# NetworkSwitch.net
KiCad netlist of a schematic drawn in Altium Designer
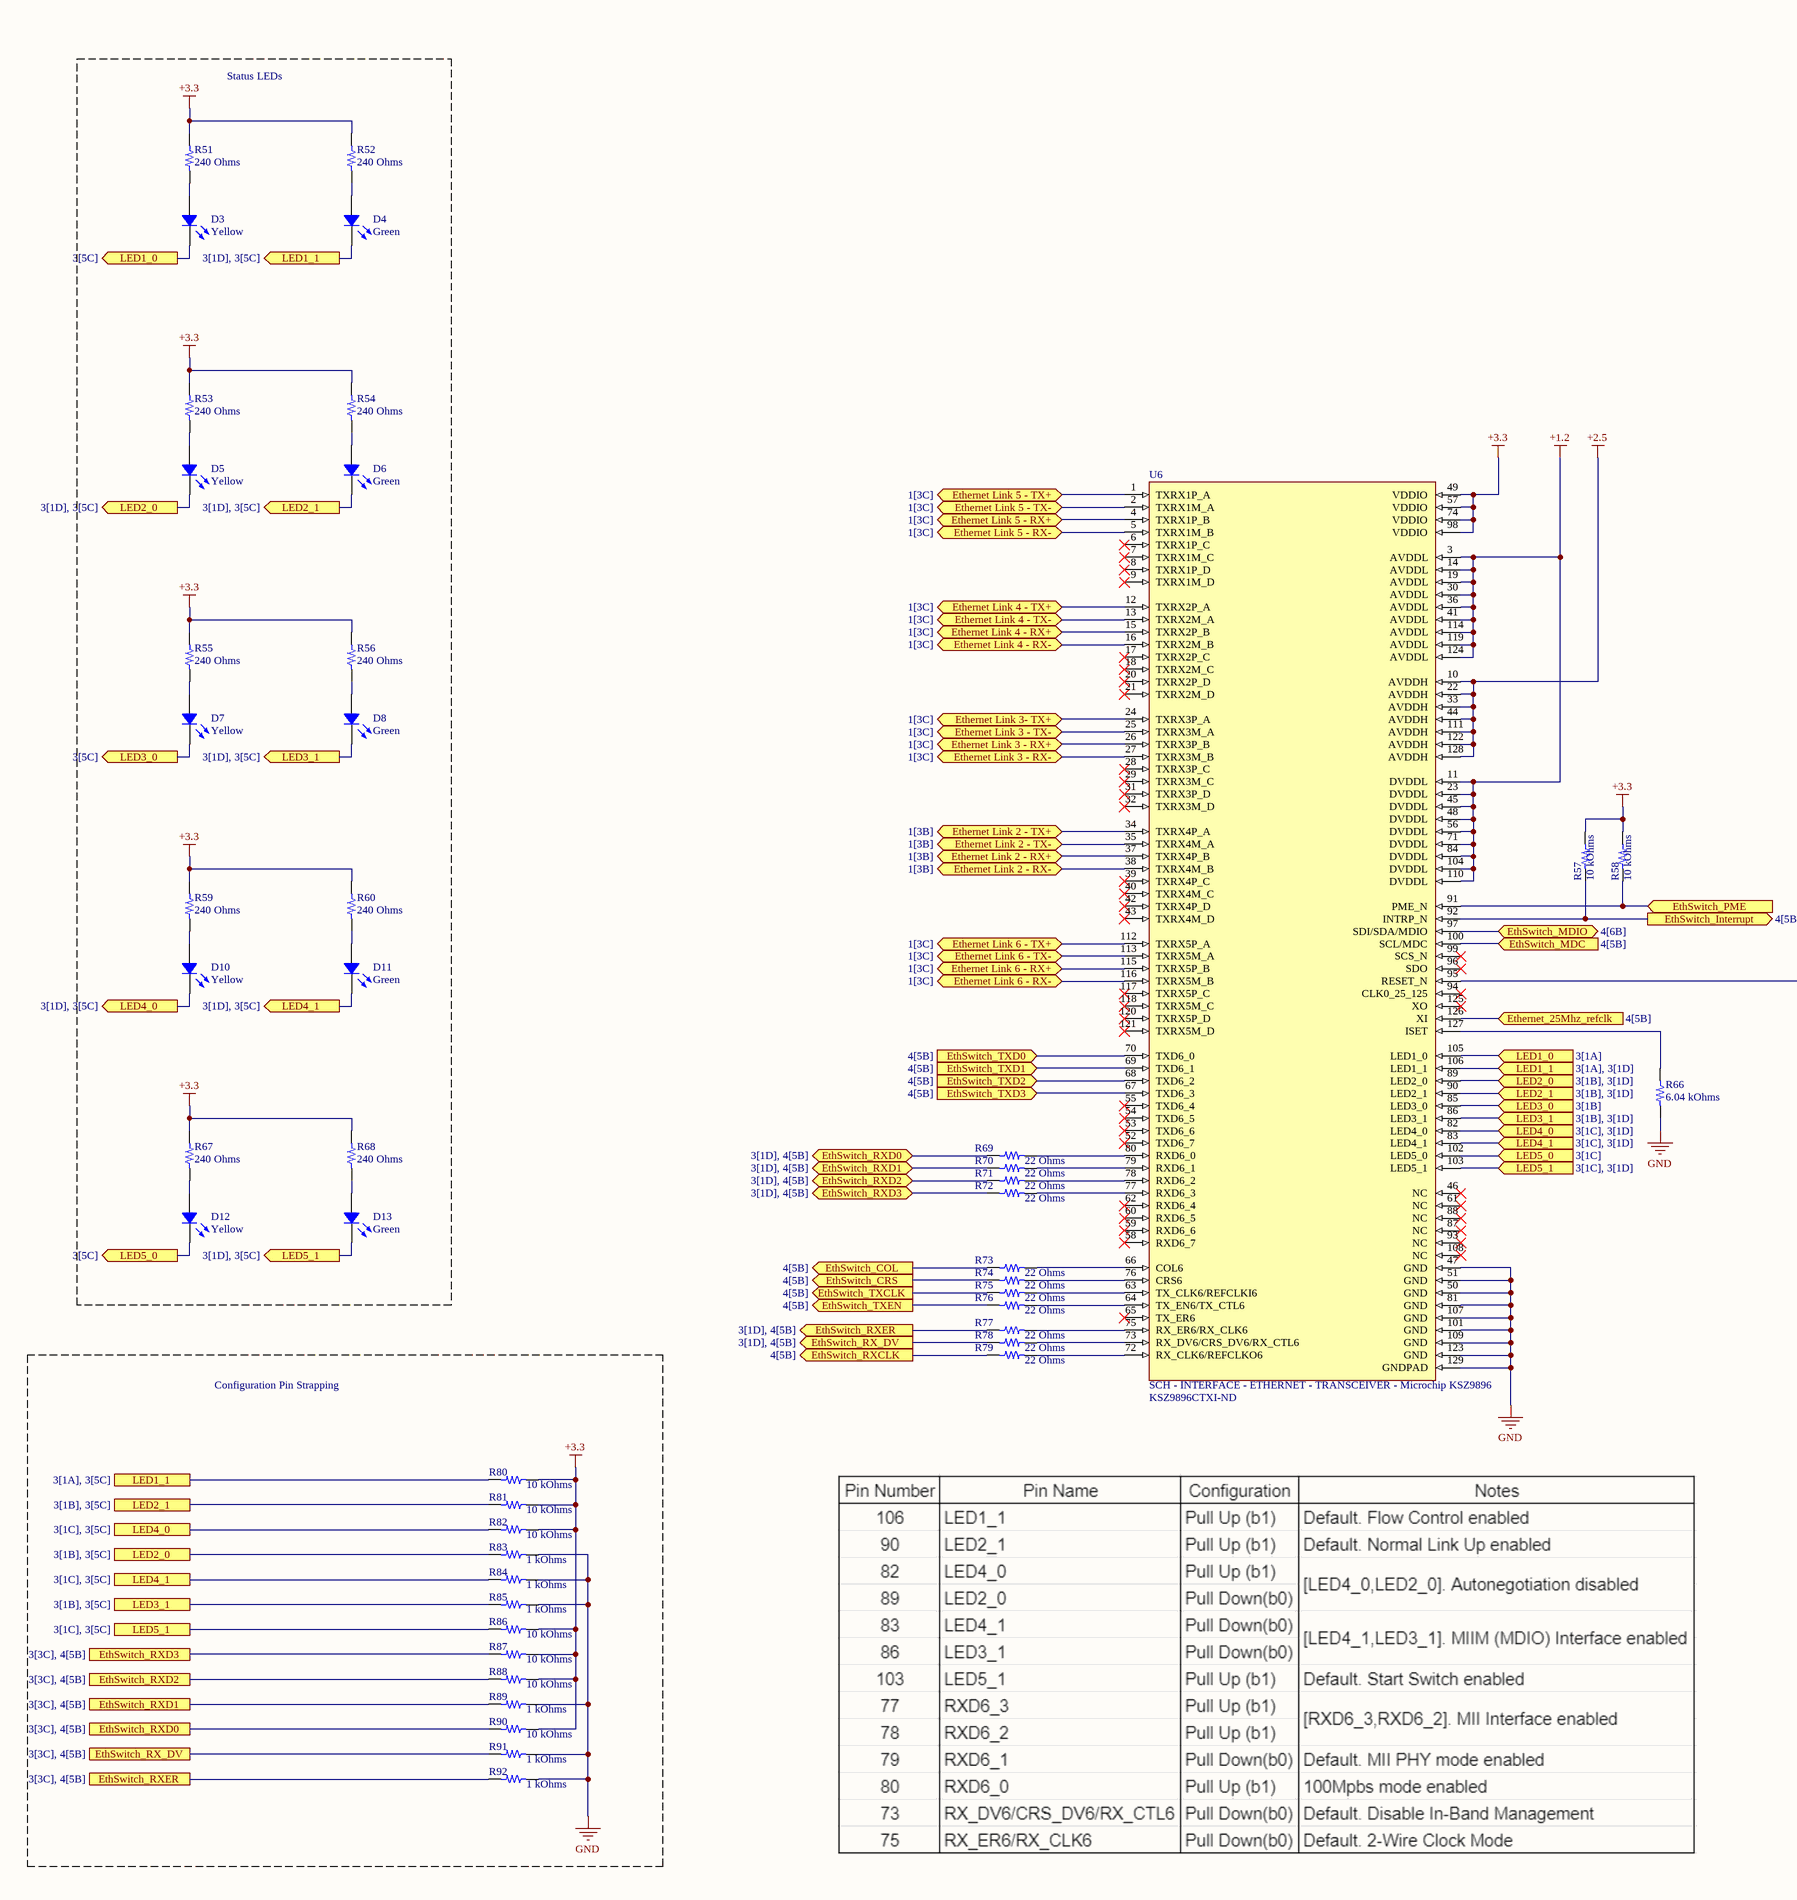
[diagram p0: NetworkSwitch.SchDoc, left]
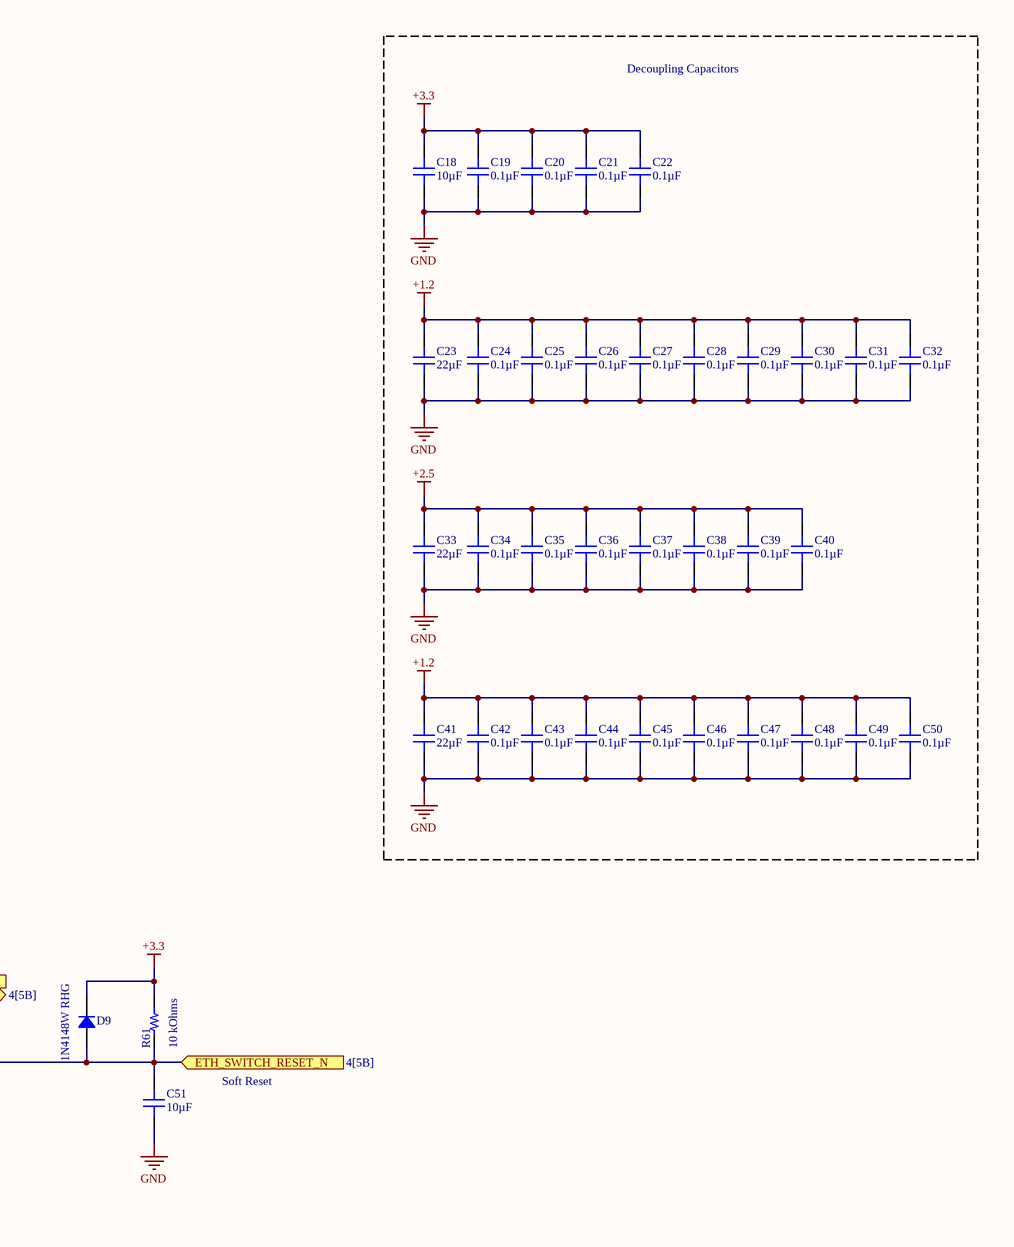
[diagram p1: NetworkSwitch.SchDoc, right]

(export (version "E")
  (design (tool "Eeschema 10.0.6"))
  (components
    (comp (ref "C18")
      (value "10µF")
      (footprint "CAP 0805_2012")
      (description "CAP CER 10UF 16V X5R 0805")
      (fields (field (name "PART NUMBER") "CC0805KKX5R7BB106") (field (name "MANUFACTURER") "Yageo"))
      (libsource (lib "Celestial Altium Library - altium_library") (part "Capacitor"))
    )
    (comp (ref "C19")
      (value "0.1µF")
      (footprint "CAP 0603_1608")
      (description "CAP CER 0.1UF 25V X7R 0603")
      (fields
        (field (name "PART NUMBER") "CL10B104KA8WPNC")
        (field (name "MANUFACTURER") "Samsung Electro-Mechanics")
      )
      (libsource (lib "Celestial Altium Library - altium_library") (part "Capacitor"))
    )
    (comp (ref "C20")
      (value "0.1µF")
      (footprint "CAP 0603_1608")
      (description "CAP CER 0.1UF 25V X7R 0603")
      (fields
        (field (name "PART NUMBER") "CL10B104KA8WPNC")
        (field (name "MANUFACTURER") "Samsung Electro-Mechanics")
      )
      (libsource (lib "Celestial Altium Library - altium_library") (part "Capacitor"))
    )
    (comp (ref "C21")
      (value "0.1µF")
      (footprint "CAP 0603_1608")
      (description "CAP CER 0.1UF 25V X7R 0603")
      (fields
        (field (name "PART NUMBER") "CL10B104KA8WPNC")
        (field (name "MANUFACTURER") "Samsung Electro-Mechanics")
      )
      (libsource (lib "Celestial Altium Library - altium_library") (part "Capacitor"))
    )
    (comp (ref "C22")
      (value "0.1µF")
      (footprint "CAP 0603_1608")
      (description "CAP CER 0.1UF 25V X7R 0603")
      (fields
        (field (name "PART NUMBER") "CL10B104KA8WPNC")
        (field (name "MANUFACTURER") "Samsung Electro-Mechanics")
      )
      (libsource (lib "Celestial Altium Library - altium_library") (part "Capacitor"))
    )
    (comp (ref "C23")
      (value "22µF")
      (footprint "CAP 0805_2012")
      (description "CAP CER 22UF 10V X5R 0805")
      (fields
        (field (name "PART NUMBER") "CL21A226KPCLRNC")
        (field (name "MANUFACTURER") "Samsung Electro-Mechanics")
      )
      (libsource (lib "Celestial Altium Library - altium_library") (part "Capacitor"))
    )
    (comp (ref "C24")
      (value "0.1µF")
      (footprint "CAP 0603_1608")
      (description "CAP CER 0.1UF 25V X7R 0603")
      (fields
        (field (name "PART NUMBER") "CL10B104KA8WPNC")
        (field (name "MANUFACTURER") "Samsung Electro-Mechanics")
      )
      (libsource (lib "Celestial Altium Library - altium_library") (part "Capacitor"))
    )
    (comp (ref "C25")
      (value "0.1µF")
      (footprint "CAP 0603_1608")
      (description "CAP CER 0.1UF 25V X7R 0603")
      (fields
        (field (name "PART NUMBER") "CL10B104KA8WPNC")
        (field (name "MANUFACTURER") "Samsung Electro-Mechanics")
      )
      (libsource (lib "Celestial Altium Library - altium_library") (part "Capacitor"))
    )
    (comp (ref "C26")
      (value "0.1µF")
      (footprint "CAP 0603_1608")
      (description "CAP CER 0.1UF 25V X7R 0603")
      (fields
        (field (name "PART NUMBER") "CL10B104KA8WPNC")
        (field (name "MANUFACTURER") "Samsung Electro-Mechanics")
      )
      (libsource (lib "Celestial Altium Library - altium_library") (part "Capacitor"))
    )
    (comp (ref "C27")
      (value "0.1µF")
      (footprint "CAP 0603_1608")
      (description "CAP CER 0.1UF 25V X7R 0603")
      (fields
        (field (name "PART NUMBER") "CL10B104KA8WPNC")
        (field (name "MANUFACTURER") "Samsung Electro-Mechanics")
      )
      (libsource (lib "Celestial Altium Library - altium_library") (part "Capacitor"))
    )
    (comp (ref "C28")
      (value "0.1µF")
      (footprint "CAP 0603_1608")
      (description "CAP CER 0.1UF 25V X7R 0603")
      (fields
        (field (name "PART NUMBER") "CL10B104KA8WPNC")
        (field (name "MANUFACTURER") "Samsung Electro-Mechanics")
      )
      (libsource (lib "Celestial Altium Library - altium_library") (part "Capacitor"))
    )
    (comp (ref "C29")
      (value "0.1µF")
      (footprint "CAP 0603_1608")
      (description "CAP CER 0.1UF 25V X7R 0603")
      (fields
        (field (name "PART NUMBER") "CL10B104KA8WPNC")
        (field (name "MANUFACTURER") "Samsung Electro-Mechanics")
      )
      (libsource (lib "Celestial Altium Library - altium_library") (part "Capacitor"))
    )
    (comp (ref "C30")
      (value "0.1µF")
      (footprint "CAP 0603_1608")
      (description "CAP CER 0.1UF 25V X7R 0603")
      (fields
        (field (name "PART NUMBER") "CL10B104KA8WPNC")
        (field (name "MANUFACTURER") "Samsung Electro-Mechanics")
      )
      (libsource (lib "Celestial Altium Library - altium_library") (part "Capacitor"))
    )
    (comp (ref "C31")
      (value "0.1µF")
      (footprint "CAP 0603_1608")
      (description "CAP CER 0.1UF 25V X7R 0603")
      (fields
        (field (name "PART NUMBER") "CL10B104KA8WPNC")
        (field (name "MANUFACTURER") "Samsung Electro-Mechanics")
      )
      (libsource (lib "Celestial Altium Library - altium_library") (part "Capacitor"))
    )
    (comp (ref "C32")
      (value "0.1µF")
      (footprint "CAP 0603_1608")
      (description "CAP CER 0.1UF 25V X7R 0603")
      (fields
        (field (name "PART NUMBER") "CL10B104KA8WPNC")
        (field (name "MANUFACTURER") "Samsung Electro-Mechanics")
      )
      (libsource (lib "Celestial Altium Library - altium_library") (part "Capacitor"))
    )
    (comp (ref "C33")
      (value "22µF")
      (footprint "CAP 0805_2012")
      (description "CAP CER 22UF 10V X5R 0805")
      (fields
        (field (name "PART NUMBER") "CL21A226KPCLRNC")
        (field (name "MANUFACTURER") "Samsung Electro-Mechanics")
      )
      (libsource (lib "Celestial Altium Library - altium_library") (part "Capacitor"))
    )
    (comp (ref "C34")
      (value "0.1µF")
      (footprint "CAP 0603_1608")
      (description "CAP CER 0.1UF 25V X7R 0603")
      (fields
        (field (name "PART NUMBER") "CL10B104KA8WPNC")
        (field (name "MANUFACTURER") "Samsung Electro-Mechanics")
      )
      (libsource (lib "Celestial Altium Library - altium_library") (part "Capacitor"))
    )
    (comp (ref "C35")
      (value "0.1µF")
      (footprint "CAP 0603_1608")
      (description "CAP CER 0.1UF 25V X7R 0603")
      (fields
        (field (name "PART NUMBER") "CL10B104KA8WPNC")
        (field (name "MANUFACTURER") "Samsung Electro-Mechanics")
      )
      (libsource (lib "Celestial Altium Library - altium_library") (part "Capacitor"))
    )
    (comp (ref "C36")
      (value "0.1µF")
      (footprint "CAP 0603_1608")
      (description "CAP CER 0.1UF 25V X7R 0603")
      (fields
        (field (name "PART NUMBER") "CL10B104KA8WPNC")
        (field (name "MANUFACTURER") "Samsung Electro-Mechanics")
      )
      (libsource (lib "Celestial Altium Library - altium_library") (part "Capacitor"))
    )
    (comp (ref "C37")
      (value "0.1µF")
      (footprint "CAP 0603_1608")
      (description "CAP CER 0.1UF 25V X7R 0603")
      (fields
        (field (name "PART NUMBER") "CL10B104KA8WPNC")
        (field (name "MANUFACTURER") "Samsung Electro-Mechanics")
      )
      (libsource (lib "Celestial Altium Library - altium_library") (part "Capacitor"))
    )
    (comp (ref "C38")
      (value "0.1µF")
      (footprint "CAP 0603_1608")
      (description "CAP CER 0.1UF 25V X7R 0603")
      (fields
        (field (name "PART NUMBER") "CL10B104KA8WPNC")
        (field (name "MANUFACTURER") "Samsung Electro-Mechanics")
      )
      (libsource (lib "Celestial Altium Library - altium_library") (part "Capacitor"))
    )
    (comp (ref "C39")
      (value "0.1µF")
      (footprint "CAP 0603_1608")
      (description "CAP CER 0.1UF 25V X7R 0603")
      (fields
        (field (name "PART NUMBER") "CL10B104KA8WPNC")
        (field (name "MANUFACTURER") "Samsung Electro-Mechanics")
      )
      (libsource (lib "Celestial Altium Library - altium_library") (part "Capacitor"))
    )
    (comp (ref "C40")
      (value "0.1µF")
      (footprint "CAP 0603_1608")
      (description "CAP CER 0.1UF 25V X7R 0603")
      (fields
        (field (name "PART NUMBER") "CL10B104KA8WPNC")
        (field (name "MANUFACTURER") "Samsung Electro-Mechanics")
      )
      (libsource (lib "Celestial Altium Library - altium_library") (part "Capacitor"))
    )
    (comp (ref "C41")
      (value "22µF")
      (footprint "CAP 0805_2012")
      (description "CAP CER 22UF 10V X5R 0805")
      (fields
        (field (name "PART NUMBER") "CL21A226KPCLRNC")
        (field (name "MANUFACTURER") "Samsung Electro-Mechanics")
      )
      (libsource (lib "Celestial Altium Library - altium_library") (part "Capacitor"))
    )
    (comp (ref "C42")
      (value "0.1µF")
      (footprint "CAP 0603_1608")
      (description "CAP CER 0.1UF 25V X7R 0603")
      (fields
        (field (name "PART NUMBER") "CL10B104KA8WPNC")
        (field (name "MANUFACTURER") "Samsung Electro-Mechanics")
      )
      (libsource (lib "Celestial Altium Library - altium_library") (part "Capacitor"))
    )
    (comp (ref "C43")
      (value "0.1µF")
      (footprint "CAP 0603_1608")
      (description "CAP CER 0.1UF 25V X7R 0603")
      (fields
        (field (name "PART NUMBER") "CL10B104KA8WPNC")
        (field (name "MANUFACTURER") "Samsung Electro-Mechanics")
      )
      (libsource (lib "Celestial Altium Library - altium_library") (part "Capacitor"))
    )
    (comp (ref "C44")
      (value "0.1µF")
      (footprint "CAP 0603_1608")
      (description "CAP CER 0.1UF 25V X7R 0603")
      (fields
        (field (name "PART NUMBER") "CL10B104KA8WPNC")
        (field (name "MANUFACTURER") "Samsung Electro-Mechanics")
      )
      (libsource (lib "Celestial Altium Library - altium_library") (part "Capacitor"))
    )
    (comp (ref "C45")
      (value "0.1µF")
      (footprint "CAP 0603_1608")
      (description "CAP CER 0.1UF 25V X7R 0603")
      (fields
        (field (name "PART NUMBER") "CL10B104KA8WPNC")
        (field (name "MANUFACTURER") "Samsung Electro-Mechanics")
      )
      (libsource (lib "Celestial Altium Library - altium_library") (part "Capacitor"))
    )
    (comp (ref "C46")
      (value "0.1µF")
      (footprint "CAP 0603_1608")
      (description "CAP CER 0.1UF 25V X7R 0603")
      (fields
        (field (name "PART NUMBER") "CL10B104KA8WPNC")
        (field (name "MANUFACTURER") "Samsung Electro-Mechanics")
      )
      (libsource (lib "Celestial Altium Library - altium_library") (part "Capacitor"))
    )
    (comp (ref "C47")
      (value "0.1µF")
      (footprint "CAP 0603_1608")
      (description "CAP CER 0.1UF 25V X7R 0603")
      (fields
        (field (name "PART NUMBER") "CL10B104KA8WPNC")
        (field (name "MANUFACTURER") "Samsung Electro-Mechanics")
      )
      (libsource (lib "Celestial Altium Library - altium_library") (part "Capacitor"))
    )
    (comp (ref "C48")
      (value "0.1µF")
      (footprint "CAP 0603_1608")
      (description "CAP CER 0.1UF 25V X7R 0603")
      (fields
        (field (name "PART NUMBER") "CL10B104KA8WPNC")
        (field (name "MANUFACTURER") "Samsung Electro-Mechanics")
      )
      (libsource (lib "Celestial Altium Library - altium_library") (part "Capacitor"))
    )
    (comp (ref "C49")
      (value "0.1µF")
      (footprint "CAP 0603_1608")
      (description "CAP CER 0.1UF 25V X7R 0603")
      (fields
        (field (name "PART NUMBER") "CL10B104KA8WPNC")
        (field (name "MANUFACTURER") "Samsung Electro-Mechanics")
      )
      (libsource (lib "Celestial Altium Library - altium_library") (part "Capacitor"))
    )
    (comp (ref "C50")
      (value "0.1µF")
      (footprint "CAP 0603_1608")
      (description "CAP CER 0.1UF 25V X7R 0603")
      (fields
        (field (name "PART NUMBER") "CL10B104KA8WPNC")
        (field (name "MANUFACTURER") "Samsung Electro-Mechanics")
      )
      (libsource (lib "Celestial Altium Library - altium_library") (part "Capacitor"))
    )
    (comp (ref "C51")
      (value "10µF")
      (footprint "CAP 0805_2012")
      (description "CAP CER 10UF 16V X5R 0805")
      (fields (field (name "PART NUMBER") "CC0805KKX5R7BB106") (field (name "MANUFACTURER") "Yageo"))
      (libsource (lib "Celestial Altium Library - altium_library") (part "Capacitor"))
    )
    (comp (ref "D3")
      (value "Yellow")
      (footprint "LED 0603_1608 YELLOW")
      (description "LED YELLOW CLEAR SMD")
      (fields (field (name "PART NUMBER") "LTST-C191KSKT") (field (name "MANUFACTURER") "Lite-On Inc."))
      (libsource (lib "Celestial Altium Library - altium_library") (part "LED"))
    )
    (comp (ref "D4")
      (value "Green")
      (footprint "LED 0603_1608 GREEN")
      (description "LED GREEN CLEAR CHIP SMD")
      (fields (field (name "PART NUMBER") "LTST-C193KGKT-5A") (field (name "MANUFACTURER") "Lite-On Inc."))
      (libsource (lib "Celestial Altium Library - altium_library") (part "LED"))
    )
    (comp (ref "D5")
      (value "Yellow")
      (footprint "LED 0603_1608 YELLOW")
      (description "LED YELLOW CLEAR SMD")
      (fields (field (name "PART NUMBER") "LTST-C191KSKT") (field (name "MANUFACTURER") "Lite-On Inc."))
      (libsource (lib "Celestial Altium Library - altium_library") (part "LED"))
    )
    (comp (ref "D6")
      (value "Green")
      (footprint "LED 0603_1608 GREEN")
      (description "LED GREEN CLEAR CHIP SMD")
      (fields (field (name "PART NUMBER") "LTST-C193KGKT-5A") (field (name "MANUFACTURER") "Lite-On Inc."))
      (libsource (lib "Celestial Altium Library - altium_library") (part "LED"))
    )
    (comp (ref "D7")
      (value "Yellow")
      (footprint "LED 0603_1608 YELLOW")
      (description "LED YELLOW CLEAR SMD")
      (fields (field (name "PART NUMBER") "LTST-C191KSKT") (field (name "MANUFACTURER") "Lite-On Inc."))
      (libsource (lib "Celestial Altium Library - altium_library") (part "LED"))
    )
    (comp (ref "D8")
      (value "Green")
      (footprint "LED 0603_1608 GREEN")
      (description "LED GREEN CLEAR CHIP SMD")
      (fields (field (name "PART NUMBER") "LTST-C193KGKT-5A") (field (name "MANUFACTURER") "Lite-On Inc."))
      (libsource (lib "Celestial Altium Library - altium_library") (part "LED"))
    )
    (comp (ref "D9")
      (value "1N4148W RHG")
      (footprint "SOD123F")
      (description "DIODE GEN PURP 100V 150MA SOD123")
      (fields (field (name "MANUFACTURER") "Taiwan Semiconductor Corporation"))
      (libsource (lib "Celestial Altium Library - altium_library") (part "Diode"))
    )
    (comp (ref "D10")
      (value "Yellow")
      (footprint "LED 0603_1608 YELLOW")
      (description "LED YELLOW CLEAR SMD")
      (fields (field (name "PART NUMBER") "LTST-C191KSKT") (field (name "MANUFACTURER") "Lite-On Inc."))
      (libsource (lib "Celestial Altium Library - altium_library") (part "LED"))
    )
    (comp (ref "D11")
      (value "Green")
      (footprint "LED 0603_1608 GREEN")
      (description "LED GREEN CLEAR CHIP SMD")
      (fields (field (name "PART NUMBER") "LTST-C193KGKT-5A") (field (name "MANUFACTURER") "Lite-On Inc."))
      (libsource (lib "Celestial Altium Library - altium_library") (part "LED"))
    )
    (comp (ref "D12")
      (value "Yellow")
      (footprint "LED 0603_1608 YELLOW")
      (description "LED YELLOW CLEAR SMD")
      (fields (field (name "PART NUMBER") "LTST-C191KSKT") (field (name "MANUFACTURER") "Lite-On Inc."))
      (libsource (lib "Celestial Altium Library - altium_library") (part "LED"))
    )
    (comp (ref "D13")
      (value "Green")
      (footprint "LED 0603_1608 GREEN")
      (description "LED GREEN CLEAR CHIP SMD")
      (fields (field (name "PART NUMBER") "LTST-C193KGKT-5A") (field (name "MANUFACTURER") "Lite-On Inc."))
      (libsource (lib "Celestial Altium Library - altium_library") (part "LED"))
    )
    (comp (ref "R51")
      (value "240 Ohms")
      (footprint "RES 0603_1608")
      (description "RES 240 OHM 5% 1/10W 0603")
      (fields
        (field (name "PART NUMBER") "RMCF0603JT240R")
        (field (name "MANUFACTURER") "Stackpole Electronics Inc")
      )
      (libsource (lib "Celestial Altium Library - altium_library") (part "Resistor"))
    )
    (comp (ref "R52")
      (value "240 Ohms")
      (footprint "RES 0603_1608")
      (description "RES 240 OHM 5% 1/10W 0603")
      (fields
        (field (name "PART NUMBER") "RMCF0603JT240R")
        (field (name "MANUFACTURER") "Stackpole Electronics Inc")
      )
      (libsource (lib "Celestial Altium Library - altium_library") (part "Resistor"))
    )
    (comp (ref "R53")
      (value "240 Ohms")
      (footprint "RES 0603_1608")
      (description "RES 240 OHM 5% 1/10W 0603")
      (fields
        (field (name "PART NUMBER") "RMCF0603JT240R")
        (field (name "MANUFACTURER") "Stackpole Electronics Inc")
      )
      (libsource (lib "Celestial Altium Library - altium_library") (part "Resistor"))
    )
    (comp (ref "R54")
      (value "240 Ohms")
      (footprint "RES 0603_1608")
      (description "RES 240 OHM 5% 1/10W 0603")
      (fields
        (field (name "PART NUMBER") "RMCF0603JT240R")
        (field (name "MANUFACTURER") "Stackpole Electronics Inc")
      )
      (libsource (lib "Celestial Altium Library - altium_library") (part "Resistor"))
    )
    (comp (ref "R55")
      (value "240 Ohms")
      (footprint "RES 0603_1608")
      (description "RES 240 OHM 5% 1/10W 0603")
      (fields
        (field (name "PART NUMBER") "RMCF0603JT240R")
        (field (name "MANUFACTURER") "Stackpole Electronics Inc")
      )
      (libsource (lib "Celestial Altium Library - altium_library") (part "Resistor"))
    )
    (comp (ref "R56")
      (value "240 Ohms")
      (footprint "RES 0603_1608")
      (description "RES 240 OHM 5% 1/10W 0603")
      (fields
        (field (name "PART NUMBER") "RMCF0603JT240R")
        (field (name "MANUFACTURER") "Stackpole Electronics Inc")
      )
      (libsource (lib "Celestial Altium Library - altium_library") (part "Resistor"))
    )
    (comp (ref "R57")
      (value "10 kOhms")
      (footprint "RES 0603_1608")
      (description "RES 10K OHM 5% 1/10W 0603")
      (fields
        (field (name "PART NUMBER") "RMCF0603JT10K0")
        (field (name "MANUFACTURER") "Stackpole Electronics Inc")
      )
      (libsource (lib "Celestial Altium Library - altium_library") (part "Resistor"))
    )
    (comp (ref "R58")
      (value "10 kOhms")
      (footprint "RES 0603_1608")
      (description "RES 10K OHM 5% 1/10W 0603")
      (fields
        (field (name "PART NUMBER") "RMCF0603JT10K0")
        (field (name "MANUFACTURER") "Stackpole Electronics Inc")
      )
      (libsource (lib "Celestial Altium Library - altium_library") (part "Resistor"))
    )
    (comp (ref "R59")
      (value "240 Ohms")
      (footprint "RES 0603_1608")
      (description "RES 240 OHM 5% 1/10W 0603")
      (fields
        (field (name "PART NUMBER") "RMCF0603JT240R")
        (field (name "MANUFACTURER") "Stackpole Electronics Inc")
      )
      (libsource (lib "Celestial Altium Library - altium_library") (part "Resistor"))
    )
    (comp (ref "R60")
      (value "240 Ohms")
      (footprint "RES 0603_1608")
      (description "RES 240 OHM 5% 1/10W 0603")
      (fields
        (field (name "PART NUMBER") "RMCF0603JT240R")
        (field (name "MANUFACTURER") "Stackpole Electronics Inc")
      )
      (libsource (lib "Celestial Altium Library - altium_library") (part "Resistor"))
    )
    (comp (ref "R61")
      (value "10 kOhms")
      (footprint "RES 0603_1608")
      (description "RES 10K OHM 5% 1/10W 0603")
      (fields
        (field (name "PART NUMBER") "RMCF0603JT10K0")
        (field (name "MANUFACTURER") "Stackpole Electronics Inc")
      )
      (libsource (lib "Celestial Altium Library - altium_library") (part "Resistor"))
    )
    (comp (ref "R66")
      (value "6.04 kOhms")
      (footprint "RES 0603_1608")
      (description "RES 6.04K OHM 1% 1/10W 0603")
      (fields
        (field (name "PART NUMBER") "RMCF0603FT6K04")
        (field (name "MANUFACTURER") "Stackpole Electronics Inc")
      )
      (libsource (lib "Celestial Altium Library - altium_library") (part "Resistor"))
    )
    (comp (ref "R67")
      (value "240 Ohms")
      (footprint "RES 0603_1608")
      (description "RES 240 OHM 5% 1/10W 0603")
      (fields
        (field (name "PART NUMBER") "RMCF0603JT240R")
        (field (name "MANUFACTURER") "Stackpole Electronics Inc")
      )
      (libsource (lib "Celestial Altium Library - altium_library") (part "Resistor"))
    )
    (comp (ref "R68")
      (value "240 Ohms")
      (footprint "RES 0603_1608")
      (description "RES 240 OHM 5% 1/10W 0603")
      (fields
        (field (name "PART NUMBER") "RMCF0603JT240R")
        (field (name "MANUFACTURER") "Stackpole Electronics Inc")
      )
      (libsource (lib "Celestial Altium Library - altium_library") (part "Resistor"))
    )
    (comp (ref "R69")
      (value "22 Ohms")
      (footprint "RES 0603_1608")
      (description "RES 22 OHM 1% 1/10W 0603")
      (fields
        (field (name "PART NUMBER") "RMCF0603FT22R0")
        (field (name "MANUFACTURER") "Stackpole Electronics Inc")
      )
      (libsource (lib "Celestial Altium Library - altium_library") (part "Resistor"))
    )
    (comp (ref "R70")
      (value "22 Ohms")
      (footprint "RES 0603_1608")
      (description "RES 22 OHM 1% 1/10W 0603")
      (fields
        (field (name "PART NUMBER") "RMCF0603FT22R0")
        (field (name "MANUFACTURER") "Stackpole Electronics Inc")
      )
      (libsource (lib "Celestial Altium Library - altium_library") (part "Resistor"))
    )
    (comp (ref "R71")
      (value "22 Ohms")
      (footprint "RES 0603_1608")
      (description "RES 22 OHM 1% 1/10W 0603")
      (fields
        (field (name "PART NUMBER") "RMCF0603FT22R0")
        (field (name "MANUFACTURER") "Stackpole Electronics Inc")
      )
      (libsource (lib "Celestial Altium Library - altium_library") (part "Resistor"))
    )
    (comp (ref "R72")
      (value "22 Ohms")
      (footprint "RES 0603_1608")
      (description "RES 22 OHM 1% 1/10W 0603")
      (fields
        (field (name "PART NUMBER") "RMCF0603FT22R0")
        (field (name "MANUFACTURER") "Stackpole Electronics Inc")
      )
      (libsource (lib "Celestial Altium Library - altium_library") (part "Resistor"))
    )
    (comp (ref "R73")
      (value "22 Ohms")
      (footprint "RES 0603_1608")
      (description "RES 22 OHM 1% 1/10W 0603")
      (fields
        (field (name "PART NUMBER") "RMCF0603FT22R0")
        (field (name "MANUFACTURER") "Stackpole Electronics Inc")
      )
      (libsource (lib "Celestial Altium Library - altium_library") (part "Resistor"))
    )
    (comp (ref "R74")
      (value "22 Ohms")
      (footprint "RES 0603_1608")
      (description "RES 22 OHM 1% 1/10W 0603")
      (fields
        (field (name "PART NUMBER") "RMCF0603FT22R0")
        (field (name "MANUFACTURER") "Stackpole Electronics Inc")
      )
      (libsource (lib "Celestial Altium Library - altium_library") (part "Resistor"))
    )
    (comp (ref "R75")
      (value "22 Ohms")
      (footprint "RES 0603_1608")
      (description "RES 22 OHM 1% 1/10W 0603")
      (fields
        (field (name "PART NUMBER") "RMCF0603FT22R0")
        (field (name "MANUFACTURER") "Stackpole Electronics Inc")
      )
      (libsource (lib "Celestial Altium Library - altium_library") (part "Resistor"))
    )
    (comp (ref "R76")
      (value "22 Ohms")
      (footprint "RES 0603_1608")
      (description "RES 22 OHM 1% 1/10W 0603")
      (fields
        (field (name "PART NUMBER") "RMCF0603FT22R0")
        (field (name "MANUFACTURER") "Stackpole Electronics Inc")
      )
      (libsource (lib "Celestial Altium Library - altium_library") (part "Resistor"))
    )
    (comp (ref "R77")
      (value "22 Ohms")
      (footprint "RES 0603_1608")
      (description "RES 22 OHM 1% 1/10W 0603")
      (fields
        (field (name "PART NUMBER") "RMCF0603FT22R0")
        (field (name "MANUFACTURER") "Stackpole Electronics Inc")
      )
      (libsource (lib "Celestial Altium Library - altium_library") (part "Resistor"))
    )
    (comp (ref "R78")
      (value "22 Ohms")
      (footprint "RES 0603_1608")
      (description "RES 22 OHM 1% 1/10W 0603")
      (fields
        (field (name "PART NUMBER") "RMCF0603FT22R0")
        (field (name "MANUFACTURER") "Stackpole Electronics Inc")
      )
      (libsource (lib "Celestial Altium Library - altium_library") (part "Resistor"))
    )
    (comp (ref "R79")
      (value "22 Ohms")
      (footprint "RES 0603_1608")
      (description "RES 22 OHM 1% 1/10W 0603")
      (fields
        (field (name "PART NUMBER") "RMCF0603FT22R0")
        (field (name "MANUFACTURER") "Stackpole Electronics Inc")
      )
      (libsource (lib "Celestial Altium Library - altium_library") (part "Resistor"))
    )
    (comp (ref "R80")
      (value "10 kOhms")
      (footprint "RES 0603_1608")
      (description "RES 10K OHM 5% 1/10W 0603")
      (fields
        (field (name "PART NUMBER") "RMCF0603JT10K0")
        (field (name "MANUFACTURER") "Stackpole Electronics Inc")
      )
      (libsource (lib "Celestial Altium Library - altium_library") (part "Resistor"))
    )
    (comp (ref "R81")
      (value "10 kOhms")
      (footprint "RES 0603_1608")
      (description "RES 10K OHM 5% 1/10W 0603")
      (fields
        (field (name "PART NUMBER") "RMCF0603JT10K0")
        (field (name "MANUFACTURER") "Stackpole Electronics Inc")
      )
      (libsource (lib "Celestial Altium Library - altium_library") (part "Resistor"))
    )
    (comp (ref "R82")
      (value "10 kOhms")
      (footprint "RES 0603_1608")
      (description "RES 10K OHM 5% 1/10W 0603")
      (fields
        (field (name "PART NUMBER") "RMCF0603JT10K0")
        (field (name "MANUFACTURER") "Stackpole Electronics Inc")
      )
      (libsource (lib "Celestial Altium Library - altium_library") (part "Resistor"))
    )
    (comp (ref "R83")
      (value "1 kOhms")
      (footprint "RES 0603_1608")
      (description "RES 1K OHM 1% 1/8W 0603")
      (fields
        (field (name "PART NUMBER") "RNCP0603FTD1K00")
        (field (name "MANUFACTURER") "Stackpole Electronics Inc")
      )
      (libsource (lib "Celestial Altium Library - altium_library") (part "Resistor"))
    )
    (comp (ref "R84")
      (value "1 kOhms")
      (footprint "RES 0603_1608")
      (description "RES 1K OHM 1% 1/8W 0603")
      (fields
        (field (name "PART NUMBER") "RNCP0603FTD1K00")
        (field (name "MANUFACTURER") "Stackpole Electronics Inc")
      )
      (libsource (lib "Celestial Altium Library - altium_library") (part "Resistor"))
    )
    (comp (ref "R85")
      (value "1 kOhms")
      (footprint "RES 0603_1608")
      (description "RES 1K OHM 1% 1/8W 0603")
      (fields
        (field (name "PART NUMBER") "RNCP0603FTD1K00")
        (field (name "MANUFACTURER") "Stackpole Electronics Inc")
      )
      (libsource (lib "Celestial Altium Library - altium_library") (part "Resistor"))
    )
    (comp (ref "R86")
      (value "10 kOhms")
      (footprint "RES 0603_1608")
      (description "RES 10K OHM 5% 1/10W 0603")
      (fields
        (field (name "PART NUMBER") "RMCF0603JT10K0")
        (field (name "MANUFACTURER") "Stackpole Electronics Inc")
      )
      (libsource (lib "Celestial Altium Library - altium_library") (part "Resistor"))
    )
    (comp (ref "R87")
      (value "10 kOhms")
      (footprint "RES 0603_1608")
      (description "RES 10K OHM 5% 1/10W 0603")
      (fields
        (field (name "PART NUMBER") "RMCF0603JT10K0")
        (field (name "MANUFACTURER") "Stackpole Electronics Inc")
      )
      (libsource (lib "Celestial Altium Library - altium_library") (part "Resistor"))
    )
    (comp (ref "R88")
      (value "10 kOhms")
      (footprint "RES 0603_1608")
      (description "RES 10K OHM 5% 1/10W 0603")
      (fields
        (field (name "PART NUMBER") "RMCF0603JT10K0")
        (field (name "MANUFACTURER") "Stackpole Electronics Inc")
      )
      (libsource (lib "Celestial Altium Library - altium_library") (part "Resistor"))
    )
    (comp (ref "R89")
      (value "1 kOhms")
      (footprint "RES 0603_1608")
      (description "RES 1K OHM 1% 1/8W 0603")
      (fields
        (field (name "PART NUMBER") "RNCP0603FTD1K00")
        (field (name "MANUFACTURER") "Stackpole Electronics Inc")
      )
      (libsource (lib "Celestial Altium Library - altium_library") (part "Resistor"))
    )
    (comp (ref "R90")
      (value "10 kOhms")
      (footprint "RES 0603_1608")
      (description "RES 10K OHM 5% 1/10W 0603")
      (fields
        (field (name "PART NUMBER") "RMCF0603JT10K0")
        (field (name "MANUFACTURER") "Stackpole Electronics Inc")
      )
      (libsource (lib "Celestial Altium Library - altium_library") (part "Resistor"))
    )
    (comp (ref "R91")
      (value "1 kOhms")
      (footprint "RES 0603_1608")
      (description "RES 1K OHM 1% 1/8W 0603")
      (fields
        (field (name "PART NUMBER") "RNCP0603FTD1K00")
        (field (name "MANUFACTURER") "Stackpole Electronics Inc")
      )
      (libsource (lib "Celestial Altium Library - altium_library") (part "Resistor"))
    )
    (comp (ref "R92")
      (value "1 kOhms")
      (footprint "RES 0603_1608")
      (description "RES 1K OHM 1% 1/8W 0603")
      (fields
        (field (name "PART NUMBER") "RNCP0603FTD1K00")
        (field (name "MANUFACTURER") "Stackpole Electronics Inc")
      )
      (libsource (lib "Celestial Altium Library - altium_library") (part "Resistor"))
    )
    (comp (ref "U6")
      (value "SCH - INTERFACE - ETHERNET - TRANSCEIVER - Microchip KSZ9896")
      (footprint "PCB - LEADS - QFP - Microchip 128-TQFP")
      (fields (field (name "SUPPLIER PART NUMBER 1") "KSZ9896CTXI-ND"))
      (libsource (lib "HAB_ICs") (part "SCH - INTERFACE - ETHERNET - TRANSCEIVER - Microchip KSZ9896"))
    )
  )
  (nets
    (net (code "1") (name "+1.2") (class "Default")
      (node (ref "C23") (pin "2") (pinfunction "2_2") (pintype "passive"))
      (node (ref "C24") (pin "2") (pinfunction "2_2") (pintype "passive"))
      (node (ref "C25") (pin "2") (pinfunction "2_2") (pintype "passive"))
      (node (ref "C26") (pin "2") (pinfunction "2_2") (pintype "passive"))
      (node (ref "C27") (pin "2") (pinfunction "2_2") (pintype "passive"))
      (node (ref "C28") (pin "2") (pinfunction "2_2") (pintype "passive"))
      (node (ref "C29") (pin "2") (pinfunction "2_2") (pintype "passive"))
      (node (ref "C30") (pin "2") (pinfunction "2_2") (pintype "passive"))
      (node (ref "C31") (pin "2") (pinfunction "2_2") (pintype "passive"))
      (node (ref "C32") (pin "2") (pinfunction "2_2") (pintype "passive"))
      (node (ref "C41") (pin "2") (pinfunction "2_2") (pintype "passive"))
      (node (ref "C42") (pin "2") (pinfunction "2_2") (pintype "passive"))
      (node (ref "C43") (pin "2") (pinfunction "2_2") (pintype "passive"))
      (node (ref "C44") (pin "2") (pinfunction "2_2") (pintype "passive"))
      (node (ref "C45") (pin "2") (pinfunction "2_2") (pintype "passive"))
      (node (ref "C46") (pin "2") (pinfunction "2_2") (pintype "passive"))
      (node (ref "C47") (pin "2") (pinfunction "2_2") (pintype "passive"))
      (node (ref "C48") (pin "2") (pinfunction "2_2") (pintype "passive"))
      (node (ref "C49") (pin "2") (pinfunction "2_2") (pintype "passive"))
      (node (ref "C50") (pin "2") (pinfunction "2_2") (pintype "passive"))
      (node (ref "U6") (pin "104") (pinfunction "DVDDL_104") (pintype "input"))
      (node (ref "U6") (pin "11") (pinfunction "DVDDL_11") (pintype "input"))
      (node (ref "U6") (pin "110") (pinfunction "DVDDL_110") (pintype "input"))
      (node (ref "U6") (pin "114") (pinfunction "AVDDL_114") (pintype "input"))
      (node (ref "U6") (pin "119") (pinfunction "AVDDL_119") (pintype "input"))
      (node (ref "U6") (pin "124") (pinfunction "AVDDL_124") (pintype "input"))
      (node (ref "U6") (pin "14") (pinfunction "AVDDL_14") (pintype "input"))
      (node (ref "U6") (pin "19") (pinfunction "AVDDL_19") (pintype "input"))
      (node (ref "U6") (pin "23") (pinfunction "DVDDL_23") (pintype "input"))
      (node (ref "U6") (pin "3") (pinfunction "AVDDL_3") (pintype "input"))
      (node (ref "U6") (pin "30") (pinfunction "AVDDL_30") (pintype "input"))
      (node (ref "U6") (pin "36") (pinfunction "AVDDL_36") (pintype "input"))
      (node (ref "U6") (pin "41") (pinfunction "AVDDL_41") (pintype "input"))
      (node (ref "U6") (pin "45") (pinfunction "DVDDL_45") (pintype "input"))
      (node (ref "U6") (pin "48") (pinfunction "DVDDL_48") (pintype "input"))
      (node (ref "U6") (pin "56") (pinfunction "DVDDL_56") (pintype "input"))
      (node (ref "U6") (pin "71") (pinfunction "DVDDL_71") (pintype "input"))
      (node (ref "U6") (pin "84") (pinfunction "DVDDL_84") (pintype "input"))
    )
    (net (code "2") (name "+2.5") (class "Default")
      (node (ref "C33") (pin "2") (pinfunction "2_2") (pintype "passive"))
      (node (ref "C34") (pin "2") (pinfunction "2_2") (pintype "passive"))
      (node (ref "C35") (pin "2") (pinfunction "2_2") (pintype "passive"))
      (node (ref "C36") (pin "2") (pinfunction "2_2") (pintype "passive"))
      (node (ref "C37") (pin "2") (pinfunction "2_2") (pintype "passive"))
      (node (ref "C38") (pin "2") (pinfunction "2_2") (pintype "passive"))
      (node (ref "C39") (pin "2") (pinfunction "2_2") (pintype "passive"))
      (node (ref "C40") (pin "2") (pinfunction "2_2") (pintype "passive"))
      (node (ref "U6") (pin "10") (pinfunction "AVDDH_10") (pintype "input"))
      (node (ref "U6") (pin "111") (pinfunction "AVDDH_111") (pintype "input"))
      (node (ref "U6") (pin "122") (pinfunction "AVDDH_122") (pintype "input"))
      (node (ref "U6") (pin "128") (pinfunction "AVDDH_128") (pintype "input"))
      (node (ref "U6") (pin "22") (pinfunction "AVDDH_22") (pintype "input"))
      (node (ref "U6") (pin "33") (pinfunction "AVDDH_33") (pintype "input"))
      (node (ref "U6") (pin "44") (pinfunction "AVDDH_44") (pintype "input"))
    )
    (net (code "3") (name "+3.3") (class "Default")
      (node (ref "C18") (pin "2") (pinfunction "2_2") (pintype "passive"))
      (node (ref "C19") (pin "2") (pinfunction "2_2") (pintype "passive"))
      (node (ref "C20") (pin "2") (pinfunction "2_2") (pintype "passive"))
      (node (ref "C21") (pin "2") (pinfunction "2_2") (pintype "passive"))
      (node (ref "C22") (pin "2") (pinfunction "2_2") (pintype "passive"))
      (node (ref "D9") (pin "2") (pinfunction "2_2") (pintype "passive"))
      (node (ref "R51") (pin "2") (pinfunction "2_2") (pintype "passive"))
      (node (ref "R52") (pin "2") (pinfunction "2_2") (pintype "passive"))
      (node (ref "R53") (pin "2") (pinfunction "2_2") (pintype "passive"))
      (node (ref "R54") (pin "2") (pinfunction "2_2") (pintype "passive"))
      (node (ref "R55") (pin "2") (pinfunction "2_2") (pintype "passive"))
      (node (ref "R56") (pin "2") (pinfunction "2_2") (pintype "passive"))
      (node (ref "R57") (pin "2") (pinfunction "2_2") (pintype "passive"))
      (node (ref "R58") (pin "2") (pinfunction "2_2") (pintype "passive"))
      (node (ref "R59") (pin "2") (pinfunction "2_2") (pintype "passive"))
      (node (ref "R60") (pin "2") (pinfunction "2_2") (pintype "passive"))
      (node (ref "R61") (pin "2") (pinfunction "2_2") (pintype "passive"))
      (node (ref "R67") (pin "2") (pinfunction "2_2") (pintype "passive"))
      (node (ref "R68") (pin "2") (pinfunction "2_2") (pintype "passive"))
      (node (ref "R80") (pin "1") (pinfunction "1_1") (pintype "passive"))
      (node (ref "R81") (pin "1") (pinfunction "1_1") (pintype "passive"))
      (node (ref "R82") (pin "1") (pinfunction "1_1") (pintype "passive"))
      (node (ref "R86") (pin "1") (pinfunction "1_1") (pintype "passive"))
      (node (ref "R87") (pin "1") (pinfunction "1_1") (pintype "passive"))
      (node (ref "R88") (pin "1") (pinfunction "1_1") (pintype "passive"))
      (node (ref "R90") (pin "1") (pinfunction "1_1") (pintype "passive"))
      (node (ref "U6") (pin "49") (pinfunction "VDDIO_49") (pintype "input"))
      (node (ref "U6") (pin "57") (pinfunction "VDDIO_57") (pintype "input"))
      (node (ref "U6") (pin "74") (pinfunction "VDDIO_74") (pintype "input"))
      (node (ref "U6") (pin "98") (pinfunction "VDDIO_98") (pintype "input"))
    )
    (net (code "4") (name "/ETH_SWITCH_RESET_N") (class "Default")
      (node (ref "C51") (pin "2") (pinfunction "2_2") (pintype "passive"))
      (node (ref "D9") (pin "1") (pinfunction "1_1") (pintype "passive"))
      (node (ref "R61") (pin "1") (pinfunction "1_1") (pintype "passive"))
      (node (ref "U6") (pin "95") (pinfunction "RESET_N_95") (pintype "input"))
    )
    (net (code "5") (name "/EthSwitch_COL") (class "Default")
      (node (ref "R73") (pin "1") (pinfunction "1_1") (pintype "passive"))
    )
    (net (code "6") (name "/EthSwitch_CRS") (class "Default")
      (node (ref "R74") (pin "1") (pinfunction "1_1") (pintype "passive"))
    )
    (net (code "7") (name "/EthSwitch_Interrupt") (class "Default")
      (node (ref "R57") (pin "1") (pinfunction "1_1") (pintype "passive"))
      (node (ref "U6") (pin "92") (pinfunction "INTRP_N_92") (pintype "input"))
    )
    (net (code "8") (name "/EthSwitch_MDC") (class "Default")
      (node (ref "U6") (pin "100") (pinfunction "SCL/MDC_100") (pintype "input"))
    )
    (net (code "9") (name "/EthSwitch_MDIO") (class "Default")
      (node (ref "U6") (pin "97") (pinfunction "SDI/SDA/MDIO_97") (pintype "input"))
    )
    (net (code "10") (name "/EthSwitch_PME") (class "Default")
      (node (ref "R58") (pin "1") (pinfunction "1_1") (pintype "passive"))
      (node (ref "U6") (pin "91") (pinfunction "PME_N_91") (pintype "input"))
    )
    (net (code "11") (name "/EthSwitch_RXCLK") (class "Default")
      (node (ref "R79") (pin "1") (pinfunction "1_1") (pintype "passive"))
    )
    (net (code "12") (name "/EthSwitch_RXD0") (class "Default")
      (node (ref "R69") (pin "1") (pinfunction "1_1") (pintype "passive"))
      (node (ref "R90") (pin "2") (pinfunction "2_2") (pintype "passive"))
    )
    (net (code "13") (name "/EthSwitch_RXD1") (class "Default")
      (node (ref "R70") (pin "1") (pinfunction "1_1") (pintype "passive"))
      (node (ref "R89") (pin "2") (pinfunction "2_2") (pintype "passive"))
    )
    (net (code "14") (name "/EthSwitch_RXD2") (class "Default")
      (node (ref "R71") (pin "1") (pinfunction "1_1") (pintype "passive"))
      (node (ref "R88") (pin "2") (pinfunction "2_2") (pintype "passive"))
    )
    (net (code "15") (name "/EthSwitch_RXD3") (class "Default")
      (node (ref "R72") (pin "1") (pinfunction "1_1") (pintype "passive"))
      (node (ref "R87") (pin "2") (pinfunction "2_2") (pintype "passive"))
    )
    (net (code "16") (name "/EthSwitch_RXER") (class "Default")
      (node (ref "R77") (pin "1") (pinfunction "1_1") (pintype "passive"))
      (node (ref "R92") (pin "2") (pinfunction "2_2") (pintype "passive"))
    )
    (net (code "17") (name "/EthSwitch_RX_DV") (class "Default")
      (node (ref "R78") (pin "1") (pinfunction "1_1") (pintype "passive"))
      (node (ref "R91") (pin "2") (pinfunction "2_2") (pintype "passive"))
    )
    (net (code "18") (name "/EthSwitch_TXCLK") (class "Default")
      (node (ref "R75") (pin "1") (pinfunction "1_1") (pintype "passive"))
    )
    (net (code "19") (name "/EthSwitch_TXD0") (class "Default")
      (node (ref "U6") (pin "70") (pinfunction "TXD6_0_70") (pintype "input"))
    )
    (net (code "20") (name "/EthSwitch_TXD1") (class "Default")
      (node (ref "U6") (pin "69") (pinfunction "TXD6_1_69") (pintype "input"))
    )
    (net (code "21") (name "/EthSwitch_TXD2") (class "Default")
      (node (ref "U6") (pin "68") (pinfunction "TXD6_2_68") (pintype "input"))
    )
    (net (code "22") (name "/EthSwitch_TXD3") (class "Default")
      (node (ref "U6") (pin "67") (pinfunction "TXD6_3_67") (pintype "input"))
    )
    (net (code "23") (name "/EthSwitch_TXEN") (class "Default")
      (node (ref "R76") (pin "1") (pinfunction "1_1") (pintype "passive"))
    )
    (net (code "24") (name "/Ethernet Link 2 - RX+") (class "Default")
      (node (ref "U6") (pin "37") (pinfunction "TXRX4P_B_37") (pintype "input"))
    )
    (net (code "25") (name "/Ethernet Link 2 - RX-") (class "Default")
      (node (ref "U6") (pin "38") (pinfunction "TXRX4M_B_38") (pintype "input"))
    )
    (net (code "26") (name "/Ethernet Link 2 - TX+") (class "Default")
      (node (ref "U6") (pin "34") (pinfunction "TXRX4P_A_34") (pintype "input"))
    )
    (net (code "27") (name "/Ethernet Link 2 - TX-") (class "Default")
      (node (ref "U6") (pin "35") (pinfunction "TXRX4M_A_35") (pintype "input"))
    )
    (net (code "28") (name "/Ethernet Link 3 - RX+") (class "Default")
      (node (ref "U6") (pin "26") (pinfunction "TXRX3P_B_26") (pintype "input"))
    )
    (net (code "29") (name "/Ethernet Link 3 - RX-") (class "Default")
      (node (ref "U6") (pin "27") (pinfunction "TXRX3M_B_27") (pintype "input"))
    )
    (net (code "30") (name "/Ethernet Link 3 - TX-") (class "Default")
      (node (ref "U6") (pin "25") (pinfunction "TXRX3M_A_25") (pintype "input"))
    )
    (net (code "31") (name "/Ethernet Link 3- TX+") (class "Default")
      (node (ref "U6") (pin "24") (pinfunction "TXRX3P_A_24") (pintype "input"))
    )
    (net (code "32") (name "/Ethernet Link 4 - RX+") (class "Default")
      (node (ref "U6") (pin "15") (pinfunction "TXRX2P_B_15") (pintype "input"))
    )
    (net (code "33") (name "/Ethernet Link 4 - RX-") (class "Default")
      (node (ref "U6") (pin "16") (pinfunction "TXRX2M_B_16") (pintype "input"))
    )
    (net (code "34") (name "/Ethernet Link 4 - TX+") (class "Default")
      (node (ref "U6") (pin "12") (pinfunction "TXRX2P_A_12") (pintype "input"))
    )
    (net (code "35") (name "/Ethernet Link 4 - TX-") (class "Default")
      (node (ref "U6") (pin "13") (pinfunction "TXRX2M_A_13") (pintype "input"))
    )
    (net (code "36") (name "/Ethernet Link 5 - RX+") (class "Default")
      (node (ref "U6") (pin "4") (pinfunction "TXRX1P_B_4") (pintype "input"))
    )
    (net (code "37") (name "/Ethernet Link 5 - RX-") (class "Default")
      (node (ref "U6") (pin "5") (pinfunction "TXRX1M_B_5") (pintype "input"))
    )
    (net (code "38") (name "/Ethernet Link 5 - TX+") (class "Default")
      (node (ref "U6") (pin "1") (pinfunction "TXRX1P_A_1") (pintype "input"))
    )
    (net (code "39") (name "/Ethernet Link 5 - TX-") (class "Default")
      (node (ref "U6") (pin "2") (pinfunction "TXRX1M_A_2") (pintype "input"))
    )
    (net (code "40") (name "/Ethernet Link 6 - RX+") (class "Default")
      (node (ref "U6") (pin "115") (pinfunction "TXRX5P_B_115") (pintype "input"))
    )
    (net (code "41") (name "/Ethernet Link 6 - RX-") (class "Default")
      (node (ref "U6") (pin "116") (pinfunction "TXRX5M_B_116") (pintype "input"))
    )
    (net (code "42") (name "/Ethernet Link 6 - TX+") (class "Default")
      (node (ref "U6") (pin "112") (pinfunction "TXRX5P_A_112") (pintype "input"))
    )
    (net (code "43") (name "/Ethernet Link 6 - TX-") (class "Default")
      (node (ref "U6") (pin "113") (pinfunction "TXRX5M_A_113") (pintype "input"))
    )
    (net (code "44") (name "/Ethernet_25Mhz_refclk") (class "Default")
      (node (ref "U6") (pin "126") (pinfunction "XI_126") (pintype "input"))
    )
    (net (code "45") (name "/LED1_0") (class "Default")
      (node (ref "D3") (pin "2") (pinfunction "2_2") (pintype "passive"))
      (node (ref "U6") (pin "105") (pinfunction "LED1_0_105") (pintype "input"))
    )
    (net (code "46") (name "/LED1_1") (class "Default")
      (node (ref "D4") (pin "2") (pinfunction "2_2") (pintype "passive"))
      (node (ref "R80") (pin "2") (pinfunction "2_2") (pintype "passive"))
      (node (ref "U6") (pin "106") (pinfunction "LED1_1_106") (pintype "input"))
    )
    (net (code "47") (name "/LED2_0") (class "Default")
      (node (ref "D5") (pin "2") (pinfunction "2_2") (pintype "passive"))
      (node (ref "R83") (pin "2") (pinfunction "2_2") (pintype "passive"))
      (node (ref "U6") (pin "89") (pinfunction "LED2_0_89") (pintype "input"))
    )
    (net (code "48") (name "/LED2_1") (class "Default")
      (node (ref "D6") (pin "2") (pinfunction "2_2") (pintype "passive"))
      (node (ref "R81") (pin "2") (pinfunction "2_2") (pintype "passive"))
      (node (ref "U6") (pin "90") (pinfunction "LED2_1_90") (pintype "input"))
    )
    (net (code "49") (name "/LED3_0") (class "Default")
      (node (ref "D7") (pin "2") (pinfunction "2_2") (pintype "passive"))
      (node (ref "U6") (pin "85") (pinfunction "LED3_0_85") (pintype "input"))
    )
    (net (code "50") (name "/LED3_1") (class "Default")
      (node (ref "D8") (pin "2") (pinfunction "2_2") (pintype "passive"))
      (node (ref "R85") (pin "2") (pinfunction "2_2") (pintype "passive"))
      (node (ref "U6") (pin "86") (pinfunction "LED3_1_86") (pintype "input"))
    )
    (net (code "51") (name "/LED4_0") (class "Default")
      (node (ref "D10") (pin "2") (pinfunction "2_2") (pintype "passive"))
      (node (ref "R82") (pin "2") (pinfunction "2_2") (pintype "passive"))
      (node (ref "U6") (pin "82") (pinfunction "LED4_0_82") (pintype "input"))
    )
    (net (code "52") (name "/LED4_1") (class "Default")
      (node (ref "D11") (pin "2") (pinfunction "2_2") (pintype "passive"))
      (node (ref "R84") (pin "2") (pinfunction "2_2") (pintype "passive"))
      (node (ref "U6") (pin "83") (pinfunction "LED4_1_83") (pintype "input"))
    )
    (net (code "53") (name "/LED5_0") (class "Default")
      (node (ref "D12") (pin "2") (pinfunction "2_2") (pintype "passive"))
      (node (ref "U6") (pin "102") (pinfunction "LED5_0_102") (pintype "input"))
    )
    (net (code "54") (name "/LED5_1") (class "Default")
      (node (ref "D13") (pin "2") (pinfunction "2_2") (pintype "passive"))
      (node (ref "R86") (pin "2") (pinfunction "2_2") (pintype "passive"))
      (node (ref "U6") (pin "103") (pinfunction "LED5_1_103") (pintype "input"))
    )
    (net (code "55") (name "GND") (class "Default")
      (node (ref "C18") (pin "1") (pinfunction "1_1") (pintype "passive"))
      (node (ref "C19") (pin "1") (pinfunction "1_1") (pintype "passive"))
      (node (ref "C20") (pin "1") (pinfunction "1_1") (pintype "passive"))
      (node (ref "C21") (pin "1") (pinfunction "1_1") (pintype "passive"))
      (node (ref "C22") (pin "1") (pinfunction "1_1") (pintype "passive"))
      (node (ref "C23") (pin "1") (pinfunction "1_1") (pintype "passive"))
      (node (ref "C24") (pin "1") (pinfunction "1_1") (pintype "passive"))
      (node (ref "C25") (pin "1") (pinfunction "1_1") (pintype "passive"))
      (node (ref "C26") (pin "1") (pinfunction "1_1") (pintype "passive"))
      (node (ref "C27") (pin "1") (pinfunction "1_1") (pintype "passive"))
      (node (ref "C28") (pin "1") (pinfunction "1_1") (pintype "passive"))
      (node (ref "C29") (pin "1") (pinfunction "1_1") (pintype "passive"))
      (node (ref "C30") (pin "1") (pinfunction "1_1") (pintype "passive"))
      (node (ref "C31") (pin "1") (pinfunction "1_1") (pintype "passive"))
      (node (ref "C32") (pin "1") (pinfunction "1_1") (pintype "passive"))
      (node (ref "C33") (pin "1") (pinfunction "1_1") (pintype "passive"))
      (node (ref "C34") (pin "1") (pinfunction "1_1") (pintype "passive"))
      (node (ref "C35") (pin "1") (pinfunction "1_1") (pintype "passive"))
      (node (ref "C36") (pin "1") (pinfunction "1_1") (pintype "passive"))
      (node (ref "C37") (pin "1") (pinfunction "1_1") (pintype "passive"))
      (node (ref "C38") (pin "1") (pinfunction "1_1") (pintype "passive"))
      (node (ref "C39") (pin "1") (pinfunction "1_1") (pintype "passive"))
      (node (ref "C40") (pin "1") (pinfunction "1_1") (pintype "passive"))
      (node (ref "C41") (pin "1") (pinfunction "1_1") (pintype "passive"))
      (node (ref "C42") (pin "1") (pinfunction "1_1") (pintype "passive"))
      (node (ref "C43") (pin "1") (pinfunction "1_1") (pintype "passive"))
      (node (ref "C44") (pin "1") (pinfunction "1_1") (pintype "passive"))
      (node (ref "C45") (pin "1") (pinfunction "1_1") (pintype "passive"))
      (node (ref "C46") (pin "1") (pinfunction "1_1") (pintype "passive"))
      (node (ref "C47") (pin "1") (pinfunction "1_1") (pintype "passive"))
      (node (ref "C48") (pin "1") (pinfunction "1_1") (pintype "passive"))
      (node (ref "C49") (pin "1") (pinfunction "1_1") (pintype "passive"))
      (node (ref "C50") (pin "1") (pinfunction "1_1") (pintype "passive"))
      (node (ref "C51") (pin "1") (pinfunction "1_1") (pintype "passive"))
      (node (ref "R66") (pin "1") (pinfunction "1_1") (pintype "passive"))
      (node (ref "R83") (pin "1") (pinfunction "1_1") (pintype "passive"))
      (node (ref "R84") (pin "1") (pinfunction "1_1") (pintype "passive"))
      (node (ref "R85") (pin "1") (pinfunction "1_1") (pintype "passive"))
      (node (ref "R89") (pin "1") (pinfunction "1_1") (pintype "passive"))
      (node (ref "R91") (pin "1") (pinfunction "1_1") (pintype "passive"))
      (node (ref "R92") (pin "1") (pinfunction "1_1") (pintype "passive"))
      (node (ref "U6") (pin "101") (pinfunction "GND_101") (pintype "input"))
      (node (ref "U6") (pin "107") (pinfunction "GND_107") (pintype "input"))
      (node (ref "U6") (pin "109") (pinfunction "GND_109") (pintype "input"))
      (node (ref "U6") (pin "123") (pinfunction "GND_123") (pintype "input"))
      (node (ref "U6") (pin "129") (pinfunction "GNDPAD_129") (pintype "input"))
      (node (ref "U6") (pin "47") (pinfunction "GND_47") (pintype "input"))
      (node (ref "U6") (pin "50") (pinfunction "GND_50") (pintype "input"))
      (node (ref "U6") (pin "51") (pinfunction "GND_51") (pintype "input"))
      (node (ref "U6") (pin "81") (pinfunction "GND_81") (pintype "input"))
    )
    (net (code "56") (name "Net-(D3-Pad1)") (class "Default")
      (node (ref "D3") (pin "1") (pinfunction "1_1") (pintype "passive"))
      (node (ref "R51") (pin "1") (pinfunction "1_1") (pintype "passive"))
    )
    (net (code "57") (name "Net-(D4-Pad1)") (class "Default")
      (node (ref "D4") (pin "1") (pinfunction "1_1") (pintype "passive"))
      (node (ref "R52") (pin "1") (pinfunction "1_1") (pintype "passive"))
    )
    (net (code "58") (name "Net-(D5-Pad1)") (class "Default")
      (node (ref "D5") (pin "1") (pinfunction "1_1") (pintype "passive"))
      (node (ref "R53") (pin "1") (pinfunction "1_1") (pintype "passive"))
    )
    (net (code "59") (name "Net-(D6-Pad1)") (class "Default")
      (node (ref "D6") (pin "1") (pinfunction "1_1") (pintype "passive"))
      (node (ref "R54") (pin "1") (pinfunction "1_1") (pintype "passive"))
    )
    (net (code "60") (name "Net-(D7-Pad1)") (class "Default")
      (node (ref "D7") (pin "1") (pinfunction "1_1") (pintype "passive"))
      (node (ref "R55") (pin "1") (pinfunction "1_1") (pintype "passive"))
    )
    (net (code "61") (name "Net-(D8-Pad1)") (class "Default")
      (node (ref "D8") (pin "1") (pinfunction "1_1") (pintype "passive"))
      (node (ref "R56") (pin "1") (pinfunction "1_1") (pintype "passive"))
    )
    (net (code "62") (name "Net-(D10-Pad1)") (class "Default")
      (node (ref "D10") (pin "1") (pinfunction "1_1") (pintype "passive"))
      (node (ref "R59") (pin "1") (pinfunction "1_1") (pintype "passive"))
    )
    (net (code "63") (name "Net-(D11-Pad1)") (class "Default")
      (node (ref "D11") (pin "1") (pinfunction "1_1") (pintype "passive"))
      (node (ref "R60") (pin "1") (pinfunction "1_1") (pintype "passive"))
    )
    (net (code "64") (name "Net-(D12-Pad1)") (class "Default")
      (node (ref "D12") (pin "1") (pinfunction "1_1") (pintype "passive"))
      (node (ref "R67") (pin "1") (pinfunction "1_1") (pintype "passive"))
    )
    (net (code "65") (name "Net-(D13-Pad1)") (class "Default")
      (node (ref "D13") (pin "1") (pinfunction "1_1") (pintype "passive"))
      (node (ref "R68") (pin "1") (pinfunction "1_1") (pintype "passive"))
    )
    (net (code "66") (name "Net-(U6-COL6)") (class "Default")
      (node (ref "R73") (pin "2") (pinfunction "2_2") (pintype "passive"))
      (node (ref "U6") (pin "66") (pinfunction "COL6_66") (pintype "input"))
    )
    (net (code "67") (name "Net-(U6-CRS6)") (class "Default")
      (node (ref "R74") (pin "2") (pinfunction "2_2") (pintype "passive"))
      (node (ref "U6") (pin "76") (pinfunction "CRS6_76") (pintype "input"))
    )
    (net (code "68") (name "Net-(U6-ISET)") (class "Default")
      (node (ref "R66") (pin "2") (pinfunction "2_2") (pintype "passive"))
      (node (ref "U6") (pin "127") (pinfunction "ISET_127") (pintype "input"))
    )
    (net (code "69") (name "Net-(U6-RXD6_0)") (class "Default")
      (node (ref "R69") (pin "2") (pinfunction "2_2") (pintype "passive"))
      (node (ref "U6") (pin "80") (pinfunction "RXD6_0_80") (pintype "input"))
    )
    (net (code "70") (name "Net-(U6-RXD6_1)") (class "Default")
      (node (ref "R70") (pin "2") (pinfunction "2_2") (pintype "passive"))
      (node (ref "U6") (pin "79") (pinfunction "RXD6_1_79") (pintype "input"))
    )
    (net (code "71") (name "Net-(U6-RXD6_2)") (class "Default")
      (node (ref "R71") (pin "2") (pinfunction "2_2") (pintype "passive"))
      (node (ref "U6") (pin "78") (pinfunction "RXD6_2_78") (pintype "input"))
    )
    (net (code "72") (name "Net-(U6-RXD6_3)") (class "Default")
      (node (ref "R72") (pin "2") (pinfunction "2_2") (pintype "passive"))
      (node (ref "U6") (pin "77") (pinfunction "RXD6_3_77") (pintype "input"))
    )
    (net (code "73") (name "Net-(U6-RX_CLK6{slash}REFCLKO6)") (class "Default")
      (node (ref "R79") (pin "2") (pinfunction "2_2") (pintype "passive"))
      (node (ref "U6") (pin "72") (pinfunction "RX_CLK6/REFCLKO6_72") (pintype "input"))
    )
    (net (code "74") (name "Net-(U6-RX_DV6{slash}CRS_DV6{slash}RX_CTL6)") (class "Default")
      (node (ref "R78") (pin "2") (pinfunction "2_2") (pintype "passive"))
      (node (ref "U6") (pin "73") (pinfunction "RX_DV6/CRS_DV6/RX_CTL6_73") (pintype "input"))
    )
    (net (code "75") (name "Net-(U6-RX_ER6{slash}RX_CLK6)") (class "Default")
      (node (ref "R77") (pin "2") (pinfunction "2_2") (pintype "passive"))
      (node (ref "U6") (pin "75") (pinfunction "RX_ER6/RX_CLK6_75") (pintype "input"))
    )
    (net (code "76") (name "Net-(U6-TX_CLK6{slash}REFCLKI6)") (class "Default")
      (node (ref "R75") (pin "2") (pinfunction "2_2") (pintype "passive"))
      (node (ref "U6") (pin "63") (pinfunction "TX_CLK6/REFCLKI6_63") (pintype "input"))
    )
    (net (code "77") (name "Net-(U6-TX_EN6{slash}TX_CTL6)") (class "Default")
      (node (ref "R76") (pin "2") (pinfunction "2_2") (pintype "passive"))
      (node (ref "U6") (pin "64") (pinfunction "TX_EN6/TX_CTL6_64") (pintype "input"))
    )
    (net (code "78") (name "unconnected-(U6-CLK0_25_125-Pad94)") (class "Default")
      (node (ref "U6") (pin "94") (pinfunction "CLK0_25_125_94") (pintype "input+no_connect"))
    )
    (net (code "79") (name "unconnected-(U6-NC-Pad46)") (class "Default")
      (node (ref "U6") (pin "46") (pinfunction "NC_46") (pintype "input+no_connect"))
    )
    (net (code "80") (name "unconnected-(U6-NC-Pad61)") (class "Default")
      (node (ref "U6") (pin "61") (pinfunction "NC_61") (pintype "input+no_connect"))
    )
    (net (code "81") (name "unconnected-(U6-NC-Pad87)") (class "Default")
      (node (ref "U6") (pin "87") (pinfunction "NC_87") (pintype "input+no_connect"))
    )
    (net (code "82") (name "unconnected-(U6-NC-Pad88)") (class "Default")
      (node (ref "U6") (pin "88") (pinfunction "NC_88") (pintype "input+no_connect"))
    )
    (net (code "83") (name "unconnected-(U6-NC-Pad93)") (class "Default")
      (node (ref "U6") (pin "93") (pinfunction "NC_93") (pintype "input+no_connect"))
    )
    (net (code "84") (name "unconnected-(U6-NC-Pad108)") (class "Default")
      (node (ref "U6") (pin "108") (pinfunction "NC_108") (pintype "input+no_connect"))
    )
    (net (code "85") (name "unconnected-(U6-RXD6_4-Pad62)") (class "Default")
      (node (ref "U6") (pin "62") (pinfunction "RXD6_4_62") (pintype "input+no_connect"))
    )
    (net (code "86") (name "unconnected-(U6-RXD6_5-Pad60)") (class "Default")
      (node (ref "U6") (pin "60") (pinfunction "RXD6_5_60") (pintype "input+no_connect"))
    )
    (net (code "87") (name "unconnected-(U6-RXD6_6-Pad59)") (class "Default")
      (node (ref "U6") (pin "59") (pinfunction "RXD6_6_59") (pintype "input+no_connect"))
    )
    (net (code "88") (name "unconnected-(U6-RXD6_7-Pad58)") (class "Default")
      (node (ref "U6") (pin "58") (pinfunction "RXD6_7_58") (pintype "input+no_connect"))
    )
    (net (code "89") (name "unconnected-(U6-SCS_N-Pad99)") (class "Default")
      (node (ref "U6") (pin "99") (pinfunction "SCS_N_99") (pintype "input+no_connect"))
    )
    (net (code "90") (name "unconnected-(U6-SDO-Pad96)") (class "Default")
      (node (ref "U6") (pin "96") (pinfunction "SDO_96") (pintype "input+no_connect"))
    )
    (net (code "91") (name "unconnected-(U6-TXD6_4-Pad55)") (class "Default")
      (node (ref "U6") (pin "55") (pinfunction "TXD6_4_55") (pintype "input+no_connect"))
    )
    (net (code "92") (name "unconnected-(U6-TXD6_5-Pad54)") (class "Default")
      (node (ref "U6") (pin "54") (pinfunction "TXD6_5_54") (pintype "input+no_connect"))
    )
    (net (code "93") (name "unconnected-(U6-TXD6_6-Pad53)") (class "Default")
      (node (ref "U6") (pin "53") (pinfunction "TXD6_6_53") (pintype "input+no_connect"))
    )
    (net (code "94") (name "unconnected-(U6-TXD6_7-Pad52)") (class "Default")
      (node (ref "U6") (pin "52") (pinfunction "TXD6_7_52") (pintype "input+no_connect"))
    )
    (net (code "95") (name "unconnected-(U6-TXRX1M_C-Pad7)") (class "Default")
      (node (ref "U6") (pin "7") (pinfunction "TXRX1M_C_7") (pintype "input+no_connect"))
    )
    (net (code "96") (name "unconnected-(U6-TXRX1M_D-Pad9)") (class "Default")
      (node (ref "U6") (pin "9") (pinfunction "TXRX1M_D_9") (pintype "input+no_connect"))
    )
    (net (code "97") (name "unconnected-(U6-TXRX1P_C-Pad6)") (class "Default")
      (node (ref "U6") (pin "6") (pinfunction "TXRX1P_C_6") (pintype "input+no_connect"))
    )
    (net (code "98") (name "unconnected-(U6-TXRX1P_D-Pad8)") (class "Default")
      (node (ref "U6") (pin "8") (pinfunction "TXRX1P_D_8") (pintype "input+no_connect"))
    )
    (net (code "99") (name "unconnected-(U6-TXRX2M_C-Pad18)") (class "Default")
      (node (ref "U6") (pin "18") (pinfunction "TXRX2M_C_18") (pintype "input+no_connect"))
    )
    (net (code "100") (name "unconnected-(U6-TXRX2M_D-Pad21)") (class "Default")
      (node (ref "U6") (pin "21") (pinfunction "TXRX2M_D_21") (pintype "input+no_connect"))
    )
    (net (code "101") (name "unconnected-(U6-TXRX2P_C-Pad17)") (class "Default")
      (node (ref "U6") (pin "17") (pinfunction "TXRX2P_C_17") (pintype "input+no_connect"))
    )
    (net (code "102") (name "unconnected-(U6-TXRX2P_D-Pad20)") (class "Default")
      (node (ref "U6") (pin "20") (pinfunction "TXRX2P_D_20") (pintype "input+no_connect"))
    )
    (net (code "103") (name "unconnected-(U6-TXRX3M_C-Pad29)") (class "Default")
      (node (ref "U6") (pin "29") (pinfunction "TXRX3M_C_29") (pintype "input+no_connect"))
    )
    (net (code "104") (name "unconnected-(U6-TXRX3M_D-Pad32)") (class "Default")
      (node (ref "U6") (pin "32") (pinfunction "TXRX3M_D_32") (pintype "input+no_connect"))
    )
    (net (code "105") (name "unconnected-(U6-TXRX3P_C-Pad28)") (class "Default")
      (node (ref "U6") (pin "28") (pinfunction "TXRX3P_C_28") (pintype "input+no_connect"))
    )
    (net (code "106") (name "unconnected-(U6-TXRX3P_D-Pad31)") (class "Default")
      (node (ref "U6") (pin "31") (pinfunction "TXRX3P_D_31") (pintype "input+no_connect"))
    )
    (net (code "107") (name "unconnected-(U6-TXRX4M_C-Pad40)") (class "Default")
      (node (ref "U6") (pin "40") (pinfunction "TXRX4M_C_40") (pintype "input+no_connect"))
    )
    (net (code "108") (name "unconnected-(U6-TXRX4M_D-Pad43)") (class "Default")
      (node (ref "U6") (pin "43") (pinfunction "TXRX4M_D_43") (pintype "input+no_connect"))
    )
    (net (code "109") (name "unconnected-(U6-TXRX4P_C-Pad39)") (class "Default")
      (node (ref "U6") (pin "39") (pinfunction "TXRX4P_C_39") (pintype "input+no_connect"))
    )
    (net (code "110") (name "unconnected-(U6-TXRX4P_D-Pad42)") (class "Default")
      (node (ref "U6") (pin "42") (pinfunction "TXRX4P_D_42") (pintype "input+no_connect"))
    )
    (net (code "111") (name "unconnected-(U6-TXRX5M_C-Pad118)") (class "Default")
      (node (ref "U6") (pin "118") (pinfunction "TXRX5M_C_118") (pintype "input+no_connect"))
    )
    (net (code "112") (name "unconnected-(U6-TXRX5M_D-Pad121)") (class "Default")
      (node (ref "U6") (pin "121") (pinfunction "TXRX5M_D_121") (pintype "input+no_connect"))
    )
    (net (code "113") (name "unconnected-(U6-TXRX5P_C-Pad117)") (class "Default")
      (node (ref "U6") (pin "117") (pinfunction "TXRX5P_C_117") (pintype "input+no_connect"))
    )
    (net (code "114") (name "unconnected-(U6-TXRX5P_D-Pad120)") (class "Default")
      (node (ref "U6") (pin "120") (pinfunction "TXRX5P_D_120") (pintype "input+no_connect"))
    )
    (net (code "115") (name "unconnected-(U6-TX_ER6-Pad65)") (class "Default")
      (node (ref "U6") (pin "65") (pinfunction "TX_ER6_65") (pintype "input+no_connect"))
    )
    (net (code "116") (name "unconnected-(U6-XO-Pad125)") (class "Default")
      (node (ref "U6") (pin "125") (pinfunction "XO_125") (pintype "input+no_connect"))
    )
  )
)
